# Bluetooth.net
KiCad netlist of a schematic drawn in Altium Designer
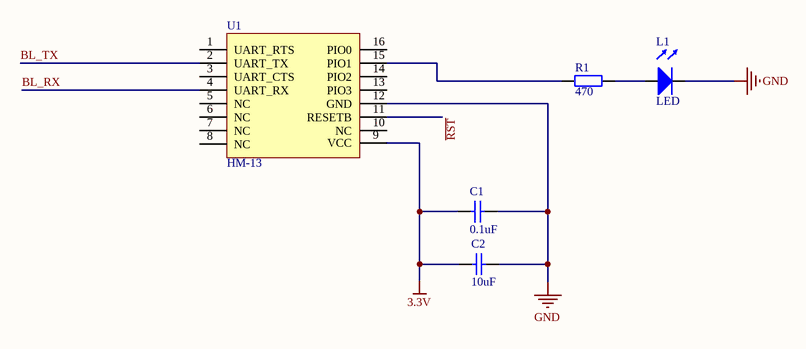
[diagram p0: Bluetooth.SchDoc]

(export (version "E")
  (design (tool "Eeschema 10.0.6"))
  (components
    (comp (ref "C1")
      (value "0.1uF")
      (footprint "0603")
      (description "ceramic")
      (libsource (lib "ToponLib") (part "Cap1"))
    )
    (comp (ref "C2")
      (value "10uF")
      (footprint "0603")
      (description "ceramic")
      (libsource (lib "ToponLib") (part "Cap1"))
    )
    (comp (ref "L1") (value "LED") (footprint "0805") (libsource (lib "ToponLib") (part "LED")))
    (comp (ref "R1") (value "470") (footprint "0603") (libsource (lib "ToponLib") (part "Res")))
    (comp (ref "U1") (value "HM-13") (footprint "HM-13") (libsource (lib "ToponLib") (part "HM-13")))
  )
  (nets
    (net (code "1") (name "/BL_RX") (class "Default")
      (node (ref "U1") (pin "4") (pinfunction "UART_RX_4") (pintype "passive"))
    )
    (net (code "2") (name "/BL_TX") (class "Default")
      (node (ref "U1") (pin "2") (pinfunction "UART_TX_2") (pintype "passive"))
    )
    (net (code "3") (name "/~{RST}") (class "Default")
      (node (ref "U1") (pin "11") (pinfunction "RESETB_11") (pintype "passive"))
    )
    (net (code "4") (name "3.3V") (class "Default")
      (node (ref "C1") (pin "2") (pinfunction "2_2") (pintype "passive"))
      (node (ref "C2") (pin "2") (pinfunction "2_2") (pintype "passive"))
      (node (ref "U1") (pin "9") (pinfunction "VCC_9") (pintype "passive"))
    )
    (net (code "5") (name "GND") (class "Default")
      (node (ref "C1") (pin "1") (pinfunction "1_1") (pintype "passive"))
      (node (ref "C2") (pin "1") (pinfunction "1_1") (pintype "passive"))
      (node (ref "L1") (pin "2") (pinfunction "K_2") (pintype "passive"))
      (node (ref "U1") (pin "12") (pinfunction "GND_12") (pintype "passive"))
    )
    (net (code "6") (name "Net-(L1-A)") (class "Default")
      (node (ref "L1") (pin "1") (pinfunction "A_1") (pintype "passive"))
      (node (ref "R1") (pin "2") (pinfunction "2_2") (pintype "passive"))
    )
    (net (code "7") (name "Net-(U1-PIO1)") (class "Default")
      (node (ref "R1") (pin "1") (pinfunction "1_1") (pintype "passive"))
      (node (ref "U1") (pin "15") (pinfunction "PIO1_15") (pintype "passive"))
    )
    (net (code "8") (name "unconnected-(U1-NC-Pad5)") (class "Default")
      (node (ref "U1") (pin "5") (pinfunction "NC_5") (pintype "passive"))
    )
    (net (code "9") (name "unconnected-(U1-NC-Pad6)") (class "Default")
      (node (ref "U1") (pin "6") (pinfunction "NC_6") (pintype "passive"))
    )
    (net (code "10") (name "unconnected-(U1-NC-Pad7)") (class "Default")
      (node (ref "U1") (pin "7") (pinfunction "NC_7") (pintype "passive"))
    )
    (net (code "11") (name "unconnected-(U1-NC-Pad8)") (class "Default")
      (node (ref "U1") (pin "8") (pinfunction "NC_8") (pintype "passive"))
    )
    (net (code "12") (name "unconnected-(U1-NC-Pad10)") (class "Default")
      (node (ref "U1") (pin "10") (pinfunction "NC_10") (pintype "passive"))
    )
    (net (code "13") (name "unconnected-(U1-PIO0-Pad16)") (class "Default")
      (node (ref "U1") (pin "16") (pinfunction "PIO0_16") (pintype "passive"))
    )
    (net (code "14") (name "unconnected-(U1-PIO2-Pad14)") (class "Default")
      (node (ref "U1") (pin "14") (pinfunction "PIO2_14") (pintype "passive"))
    )
    (net (code "15") (name "unconnected-(U1-PIO3-Pad13)") (class "Default")
      (node (ref "U1") (pin "13") (pinfunction "PIO3_13") (pintype "passive"))
    )
    (net (code "16") (name "unconnected-(U1-UART_CTS-Pad3)") (class "Default")
      (node (ref "U1") (pin "3") (pinfunction "UART_CTS_3") (pintype "passive"))
    )
    (net (code "17") (name "unconnected-(U1-UART_RTS-Pad1)") (class "Default")
      (node (ref "U1") (pin "1") (pinfunction "UART_RTS_1") (pintype "passive"))
    )
  )
)
